# Sheet2.net
KiCad netlist of a schematic drawn in Altium Designer
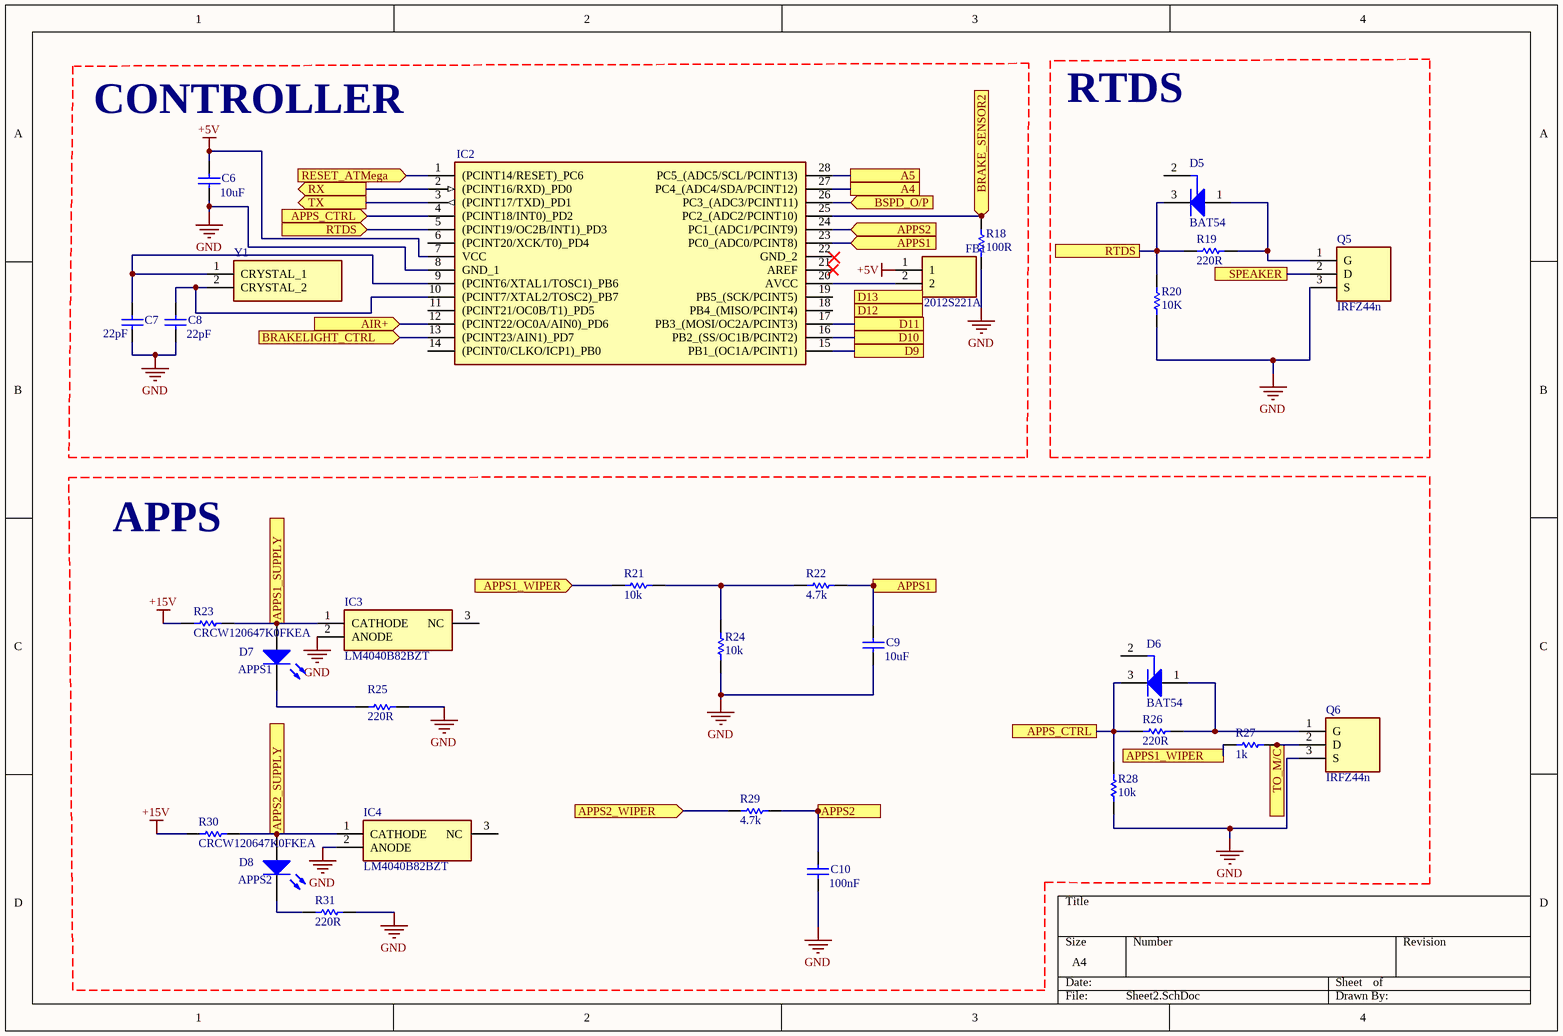
[diagram p0: Sheet2.SchDoc]

(export (version "E")
  (design (tool "Eeschema 10.0.6"))
  (components
    (comp (ref "C6")
      (value "10uF")
      (footprint "KEMT-1206-2_N")
      (description "CAP, Ceramic, 0.1 uF, +/- 10%, 50 V, -55 to 125 degC, 1206 (3216 Metric), RoHS, Tape and Reel")
      (fields (field (name "MANUFACTURER") "Kemet"))
      (libsource (lib "Schlib1_TSAL_LV_3.1") (part "CMP-1037-04202-2"))
    )
    (comp (ref "C7")
      (value "22pF")
      (footprint "KEMT-1206-2_N")
      (description "CAP, Ceramic, 0.1 uF, +/- 10%, 50 V, -55 to 125 degC, 1206 (3216 Metric), RoHS, Tape and Reel")
      (fields (field (name "MANUFACTURER") "Kemet"))
      (libsource (lib "Schlib1_TSAL_LV_3.1") (part "CMP-1037-04202-2"))
    )
    (comp (ref "C8")
      (value "22pF")
      (footprint "KEMT-1206-2_N")
      (description "CAP, Ceramic, 0.1 uF, +/- 10%, 50 V, -55 to 125 degC, 1206 (3216 Metric), RoHS, Tape and Reel")
      (fields (field (name "MANUFACTURER") "Kemet"))
      (libsource (lib "Schlib1_TSAL_LV_3.1") (part "CMP-1037-04202-2"))
    )
    (comp (ref "C9")
      (value "10uF")
      (footprint "KEMT-1206-2_N")
      (description "CAP, Ceramic, 0.1 uF, +/- 10%, 50 V, -55 to 125 degC, 1206 (3216 Metric), RoHS, Tape and Reel")
      (fields (field (name "MANUFACTURER") "Kemet"))
      (libsource (lib "Schlib1_TSAL_LV_3.1") (part "CMP-1037-04202-2"))
    )
    (comp (ref "C10")
      (value "100nF")
      (footprint "KEMT-1206-2_N")
      (description "CAP, Ceramic, 0.1 uF, +/- 10%, 50 V, -55 to 125 degC, 1206 (3216 Metric), RoHS, Tape and Reel")
      (fields (field (name "MANUFACTURER") "Kemet"))
      (libsource (lib "Schlib1_TSAL_LV_3.1") (part "CMP-1037-04202-2"))
    )
    (comp (ref "D5")
      (value "BAT54")
      (footprint "INF-SOT23_N")
      (description "Silicon Schottky Diode, SOT23, Reel, Green")
      (fields (field (name "MANUFACTURER") "Infineon"))
      (libsource (lib "Schlib1_TSAL_LV_3.1") (part "CMP-1182-00010-1"))
    )
    (comp (ref "D6")
      (value "BAT54")
      (footprint "INF-SOT23_N")
      (description "Silicon Schottky Diode, SOT23, Reel, Green")
      (fields (field (name "MANUFACTURER") "Infineon"))
      (libsource (lib "Schlib1_TSAL_LV_3.1") (part "CMP-1182-00010-1"))
    )
    (comp (ref "D7")
      (value "APPS1")
      (footprint "3.2X1.6X1.1")
      (description "Typical RED, GREEN, YELLOW, AMBER GaAs LED")
      (fields (field (name "PUBLISHER") "Altium Limited"))
      (libsource (lib "Miscellaneous Devices") (part "LED2"))
    )
    (comp (ref "D8")
      (value "APPS2")
      (footprint "3.2X1.6X1.1")
      (description "Typical RED, GREEN, YELLOW, AMBER GaAs LED")
      (fields (field (name "PUBLISHER") "Altium Limited"))
      (libsource (lib "Miscellaneous Devices") (part "LED2"))
    )
    (comp (ref "FB1")
      (value "MPZ2012S221A")
      (footprint "SamacSys:BEADC2012X105N")
      (description "Ferrite Bead")
      (fields (field (name "MOUSER PART NUMBER") "810-MPZ2012S221A"))
      (libsource (lib "*") (part "MPZ2012S221A"))
    )
    (comp (ref "IC2")
      (value "ATMEGA328-PU")
      (footprint "SamacSys:DIP1016W53P254L3468H457Q28N")
      (description "Integrated Circuit")
      (fields (field (name "MOUSER PART NUMBER") "556-ATMEGA328-PU"))
      (libsource (lib "*") (part "ATMEGA328-PU"))
    )
    (comp (ref "IC3")
      (value "LM4040B82BZT")
      (footprint "SamacSys:SOT95P237X112-3N")
      (description "Integrated Circuit")
      (fields
        (field (name "MANUFACTURER_PART_NUMBER") "LM4040B25IDBZT")
        (field (name "MOUSER PART NUMBER") "595-LM4040B25IDBZT")
      )
      (libsource (lib "*") (part "LM4040B25IDBZT"))
    )
    (comp (ref "IC4")
      (value "LM4040B82BZT")
      (footprint "SamacSys:SOT95P237X112-3N")
      (description "Integrated Circuit")
      (fields
        (field (name "MANUFACTURER_PART_NUMBER") "LM4040B25IDBZT")
        (field (name "MOUSER PART NUMBER") "595-LM4040B25IDBZT")
      )
      (libsource (lib "*") (part "LM4040B25IDBZT"))
    )
    (comp (ref "Q5")
      (value "IRFZ44n")
      (footprint "SamacSys:TO254P483X1016X2223-3P")
      (description "Transistor")
      (libsource (lib "*") (part "IRFZ44n"))
    )
    (comp (ref "Q6")
      (value "IRFZ44n")
      (footprint "SamacSys:TO254P483X1016X2223-3P")
      (description "Transistor")
      (libsource (lib "*") (part "IRFZ44n"))
    )
    (comp (ref "R18")
      (value "100R")
      (footprint "R1206")
      (fields (field (name "PART NUMBER") "CRCW120647K0FKEA") (field (name "MANUFACTURER") "Vishay Dale"))
      (libsource (lib "Schlib1") (part "RES"))
    )
    (comp (ref "R19")
      (value "220R")
      (footprint "R1206")
      (fields (field (name "PART NUMBER") "CRCW120647K0FKEA") (field (name "MANUFACTURER") "Vishay Dale"))
      (libsource (lib "Schlib1") (part "RES"))
    )
    (comp (ref "R20")
      (value "10K")
      (footprint "R1206")
      (fields (field (name "PART NUMBER") "CRCW120647K0FKEA") (field (name "MANUFACTURER") "Vishay Dale"))
      (libsource (lib "Schlib1") (part "RES"))
    )
    (comp (ref "R21")
      (value "10k")
      (footprint "R1206")
      (fields (field (name "PART NUMBER") "CRCW120647K0FKEA") (field (name "MANUFACTURER") "Vishay Dale"))
      (libsource (lib "Schlib1") (part "RES"))
    )
    (comp (ref "R22")
      (value "4.7k")
      (footprint "R1206")
      (fields (field (name "PART NUMBER") "CRCW120647K0FKEA") (field (name "MANUFACTURER") "Vishay Dale"))
      (libsource (lib "Schlib1") (part "RES"))
    )
    (comp (ref "R23")
      (value "CRCW120647K0FKEA")
      (footprint "R1206")
      (fields (field (name "MANUFACTURER") "Vishay Dale"))
      (libsource (lib "Schlib1") (part "RES"))
    )
    (comp (ref "R24")
      (value "10k")
      (footprint "R1206")
      (fields (field (name "PART NUMBER") "CRCW120647K0FKEA") (field (name "MANUFACTURER") "Vishay Dale"))
      (libsource (lib "Schlib1") (part "RES"))
    )
    (comp (ref "R25")
      (value "220R")
      (footprint "R1206")
      (fields (field (name "PART NUMBER") "CRCW120647K0FKEA") (field (name "MANUFACTURER") "Vishay Dale"))
      (libsource (lib "Schlib1") (part "RES"))
    )
    (comp (ref "R26")
      (value "220R")
      (footprint "R1206")
      (fields (field (name "PART NUMBER") "CRCW120647K0FKEA") (field (name "MANUFACTURER") "Vishay Dale"))
      (libsource (lib "Schlib1") (part "RES"))
    )
    (comp (ref "R27")
      (value "1k")
      (footprint "R1206")
      (fields (field (name "PART NUMBER") "CRCW120647K0FKEA") (field (name "MANUFACTURER") "Vishay Dale"))
      (libsource (lib "Schlib1") (part "RES"))
    )
    (comp (ref "R28")
      (value "10k")
      (footprint "R1206")
      (fields (field (name "PART NUMBER") "CRCW120647K0FKEA") (field (name "MANUFACTURER") "Vishay Dale"))
      (libsource (lib "Schlib1") (part "RES"))
    )
    (comp (ref "R29")
      (value "4.7k")
      (footprint "R1206")
      (fields (field (name "PART NUMBER") "CRCW120647K0FKEA") (field (name "MANUFACTURER") "Vishay Dale"))
      (libsource (lib "Schlib1") (part "RES"))
    )
    (comp (ref "R30")
      (value "CRCW120647K0FKEA")
      (footprint "R1206")
      (fields (field (name "MANUFACTURER") "Vishay Dale"))
      (libsource (lib "Schlib1") (part "RES"))
    )
    (comp (ref "R31")
      (value "220R")
      (footprint "R1206")
      (fields (field (name "PART NUMBER") "CRCW120647K0FKEA") (field (name "MANUFACTURER") "Vishay Dale"))
      (libsource (lib "Schlib1") (part "RES"))
    )
    (comp (ref "Y1")
      (value "ECS-160-18-4X-CKM")
      (footprint "SamacSys:ECS160184XCKM")
      (description "Crystal or Oscillator")
      (fields (field (name "MOUSER PART NUMBER") "520-ECS160-18-4X-CKM"))
      (libsource (lib "*") (part "ECS-160-18-4X-CKM"))
    )
  )
  (nets
    (net (code "1") (name "+5V") (class "Default")
      (node (ref "C6") (pin "2") (pinfunction "2_2") (pintype "passive"))
      (node (ref "FB1") (pin "1") (pinfunction "1_1") (pintype "passive"))
      (node (ref "IC2") (pin "7") (pinfunction "VCC_7") (pintype "power_in"))
    )
    (net (code "2") (name "+15V") (class "Default")
      (node (ref "R23") (pin "1") (pinfunction "1_1") (pintype "passive"))
      (node (ref "R30") (pin "1") (pinfunction "1_1") (pintype "passive"))
    )
    (net (code "3") (name "/A4") (class "Default")
      (node (ref "IC2") (pin "27") (pinfunction "PC4_(ADC4/SDA/PCINT12)_27") (pintype "passive"))
    )
    (net (code "4") (name "/A5") (class "Default")
      (node (ref "IC2") (pin "28") (pinfunction "PC5_(ADC5/SCL/PCINT13)_28") (pintype "passive"))
    )
    (net (code "5") (name "/AIR+") (class "Default")
      (node (ref "IC2") (pin "12") (pinfunction "(PCINT22/OC0A/AIN0)_PD6_12") (pintype "passive"))
    )
    (net (code "6") (name "/APPS1") (class "Default")
      (node (ref "C9") (pin "2") (pinfunction "2_2") (pintype "passive"))
      (node (ref "IC2") (pin "23") (pinfunction "PC0_(ADC0/PCINT8)_23") (pintype "passive"))
      (node (ref "R22") (pin "2") (pinfunction "2_2") (pintype "passive"))
    )
    (net (code "7") (name "/APPS1_SUPPLY") (class "Default")
      (node (ref "D7") (pin "1") (pinfunction "A_1") (pintype "passive"))
      (node (ref "IC3") (pin "1") (pinfunction "CATHODE_1") (pintype "passive"))
      (node (ref "R23") (pin "2") (pinfunction "2_2") (pintype "passive"))
    )
    (net (code "8") (name "/APPS1_WIPER") (class "Default")
      (node (ref "R21") (pin "1") (pinfunction "1_1") (pintype "passive"))
      (node (ref "R27") (pin "2") (pinfunction "2_2") (pintype "passive"))
    )
    (net (code "9") (name "/APPS2") (class "Default")
      (node (ref "C10") (pin "2") (pinfunction "2_2") (pintype "passive"))
      (node (ref "IC2") (pin "24") (pinfunction "PC1_(ADC1/PCINT9)_24") (pintype "passive"))
      (node (ref "R29") (pin "2") (pinfunction "2_2") (pintype "passive"))
    )
    (net (code "10") (name "/APPS2_SUPPLY") (class "Default")
      (node (ref "D8") (pin "1") (pinfunction "A_1") (pintype "passive"))
      (node (ref "IC4") (pin "1") (pinfunction "CATHODE_1") (pintype "passive"))
      (node (ref "R30") (pin "2") (pinfunction "2_2") (pintype "passive"))
    )
    (net (code "11") (name "/APPS2_WIPER") (class "Default")
      (node (ref "R29") (pin "1") (pinfunction "1_1") (pintype "passive"))
    )
    (net (code "12") (name "/APPS_CTRL") (class "Default")
      (node (ref "D6") (pin "3") (pinfunction "K_3") (pintype "passive"))
      (node (ref "IC2") (pin "4") (pinfunction "(PCINT18/INT0)_PD2_4") (pintype "passive"))
      (node (ref "R26") (pin "1") (pinfunction "1_1") (pintype "passive"))
      (node (ref "R28") (pin "2") (pinfunction "2_2") (pintype "passive"))
    )
    (net (code "13") (name "/BRAKELIGHT_CTRL") (class "Default")
      (node (ref "IC2") (pin "13") (pinfunction "(PCINT23/AIN1)_PD7_13") (pintype "passive"))
    )
    (net (code "14") (name "/BRAKE_SENSOR2") (class "Default")
      (node (ref "IC2") (pin "25") (pinfunction "PC2_(ADC2/PCINT10)_25") (pintype "passive"))
      (node (ref "R18") (pin "2") (pinfunction "2_2") (pintype "passive"))
    )
    (net (code "15") (name "/BSPD_O{slash}P") (class "Default")
      (node (ref "IC2") (pin "26") (pinfunction "PC3_(ADC3/PCINT11)_26") (pintype "passive"))
    )
    (net (code "16") (name "/D9") (class "Default")
      (node (ref "IC2") (pin "15") (pinfunction "PB1_(OC1A/PCINT1)_15") (pintype "passive"))
    )
    (net (code "17") (name "/D10") (class "Default")
      (node (ref "IC2") (pin "16") (pinfunction "PB2_(SS/OC1B/PCINT2)_16") (pintype "passive"))
    )
    (net (code "18") (name "/D11") (class "Default")
      (node (ref "IC2") (pin "17") (pinfunction "PB3_(MOSI/OC2A/PCINT3)_17") (pintype "passive"))
    )
    (net (code "21") (name "/RESET_ATMega") (class "Default")
      (node (ref "IC2") (pin "1") (pinfunction "(PCINT14/RESET)_PC6_1") (pintype "passive"))
    )
    (net (code "22") (name "/RTDS") (class "Default")
      (node (ref "D5") (pin "3") (pinfunction "K_3") (pintype "passive"))
      (node (ref "IC2") (pin "5") (pinfunction "(PCINT19/OC2B/INT1)_PD3_5") (pintype "passive"))
      (node (ref "R19") (pin "1") (pinfunction "1_1") (pintype "passive"))
      (node (ref "R20") (pin "2") (pinfunction "2_2") (pintype "passive"))
    )
    (net (code "23") (name "/RX") (class "Default")
      (node (ref "IC2") (pin "2") (pinfunction "(PCINT16/RXD)_PD0_2") (pintype "input"))
    )
    (net (code "24") (name "/SPEAKER") (class "Default")
      (node (ref "Q5") (pin "2") (pinfunction "D_2") (pintype "passive"))
    )
    (net (code "25") (name "/TO_M{slash}C") (class "Default")
      (node (ref "Q6") (pin "2") (pinfunction "D_2") (pintype "passive"))
      (node (ref "R27") (pin "1") (pinfunction "1_1") (pintype "passive"))
    )
    (net (code "26") (name "/TX") (class "Default")
      (node (ref "IC2") (pin "3") (pinfunction "(PCINT17/TXD)_PD1_3") (pintype "output"))
    )
    (net (code "27") (name "GND") (class "Default")
      (node (ref "C10") (pin "1") (pinfunction "1_1") (pintype "passive"))
      (node (ref "C6") (pin "1") (pinfunction "1_1") (pintype "passive"))
      (node (ref "C7") (pin "1") (pinfunction "1_1") (pintype "passive"))
      (node (ref "C8") (pin "1") (pinfunction "1_1") (pintype "passive"))
      (node (ref "C9") (pin "1") (pinfunction "1_1") (pintype "passive"))
      (node (ref "IC2") (pin "8") (pinfunction "GND_1_8") (pintype "power_in"))
      (node (ref "IC3") (pin "2") (pinfunction "ANODE_2") (pintype "passive"))
      (node (ref "IC4") (pin "2") (pinfunction "ANODE_2") (pintype "passive"))
      (node (ref "Q5") (pin "3") (pinfunction "S_3") (pintype "passive"))
      (node (ref "Q6") (pin "3") (pinfunction "S_3") (pintype "passive"))
      (node (ref "R18") (pin "1") (pinfunction "1_1") (pintype "passive"))
      (node (ref "R20") (pin "1") (pinfunction "1_1") (pintype "passive"))
      (node (ref "R24") (pin "1") (pinfunction "1_1") (pintype "passive"))
      (node (ref "R25") (pin "2") (pinfunction "2_2") (pintype "passive"))
      (node (ref "R28") (pin "1") (pinfunction "1_1") (pintype "passive"))
      (node (ref "R31") (pin "2") (pinfunction "2_2") (pintype "passive"))
    )
    (net (code "28") (name "Net-(D5-A)") (class "Default")
      (node (ref "D5") (pin "1") (pinfunction "A_1") (pintype "passive"))
      (node (ref "Q5") (pin "1") (pinfunction "G_1") (pintype "passive"))
      (node (ref "R19") (pin "2") (pinfunction "2_2") (pintype "passive"))
    )
    (net (code "29") (name "Net-(D6-A)") (class "Default")
      (node (ref "D6") (pin "1") (pinfunction "A_1") (pintype "passive"))
      (node (ref "Q6") (pin "1") (pinfunction "G_1") (pintype "passive"))
      (node (ref "R26") (pin "2") (pinfunction "2_2") (pintype "passive"))
    )
    (net (code "30") (name "Net-(D7-K)") (class "Default")
      (node (ref "D7") (pin "2") (pinfunction "K_2") (pintype "passive"))
      (node (ref "R25") (pin "1") (pinfunction "1_1") (pintype "passive"))
    )
    (net (code "31") (name "Net-(D8-K)") (class "Default")
      (node (ref "D8") (pin "2") (pinfunction "K_2") (pintype "passive"))
      (node (ref "R31") (pin "1") (pinfunction "1_1") (pintype "passive"))
    )
    (net (code "32") (name "Net-(IC2-(PCINT6{slash}XTAL1{slash}TOSC1)_PB6)") (class "Default")
      (node (ref "C7") (pin "2") (pinfunction "2_2") (pintype "passive"))
      (node (ref "IC2") (pin "9") (pinfunction "(PCINT6/XTAL1/TOSC1)_PB6_9") (pintype "passive"))
      (node (ref "Y1") (pin "1") (pinfunction "CRYSTAL_1_1") (pintype "passive"))
    )
    (net (code "33") (name "Net-(IC2-(PCINT7{slash}XTAL2{slash}TOSC2)_PB7)") (class "Default")
      (node (ref "C8") (pin "2") (pinfunction "2_2") (pintype "passive"))
      (node (ref "IC2") (pin "10") (pinfunction "(PCINT7/XTAL2/TOSC2)_PB7_10") (pintype "passive"))
      (node (ref "Y1") (pin "2") (pinfunction "CRYSTAL_2_2") (pintype "passive"))
    )
    (net (code "34") (name "Net-(IC2-AVCC)") (class "Default")
      (node (ref "FB1") (pin "2") (pinfunction "2_2") (pintype "passive"))
      (node (ref "IC2") (pin "20") (pinfunction "AVCC_20") (pintype "power_in"))
    )
    (net (code "35") (name "Net-(R21-Pad2)") (class "Default")
      (node (ref "R21") (pin "2") (pinfunction "2_2") (pintype "passive"))
      (node (ref "R22") (pin "1") (pinfunction "1_1") (pintype "passive"))
      (node (ref "R24") (pin "2") (pinfunction "2_2") (pintype "passive"))
    )
    (net (code "36") (name "unconnected-(D5-NC-Pad2)") (class "Default")
      (node (ref "D5") (pin "2") (pinfunction "NC_2") (pintype "passive"))
    )
    (net (code "37") (name "unconnected-(D6-NC-Pad2)") (class "Default")
      (node (ref "D6") (pin "2") (pinfunction "NC_2") (pintype "passive"))
    )
    (net (code "38") (name "unconnected-(IC2-(PCINT0{slash}CLKO{slash}ICP1)_PB0-Pad14)") (class "Default")
      (node (ref "IC2") (pin "14") (pinfunction "(PCINT0/CLKO/ICP1)_PB0_14") (pintype "passive"))
    )
    (net (code "39") (name "unconnected-(IC2-(PCINT20{slash}XCK{slash}T0)_PD4-Pad6)") (class "Default")
      (node (ref "IC2") (pin "6") (pinfunction "(PCINT20/XCK/T0)_PD4_6") (pintype "passive"))
    )
    (net (code "40") (name "unconnected-(IC2-(PCINT21{slash}OC0B{slash}T1)_PD5-Pad11)") (class "Default")
      (node (ref "IC2") (pin "11") (pinfunction "(PCINT21/OC0B/T1)_PD5_11") (pintype "passive"))
    )
    (net (code "41") (name "unconnected-(IC2-AREF-Pad21)") (class "Default")
      (node (ref "IC2") (pin "21") (pinfunction "AREF_21") (pintype "passive+no_connect"))
    )
    (net (code "42") (name "unconnected-(IC2-GND_2-Pad22)") (class "Default")
      (node (ref "IC2") (pin "22") (pinfunction "GND_2_22") (pintype "power_in"))
    )
    (net (code "43") (name "unconnected-(IC2-PB4_(MISO{slash}PCINT4)-Pad18)") (class "Default")
      (node (ref "IC2") (pin "18") (pinfunction "PB4_(MISO/PCINT4)_18") (pintype "passive"))
    )
    (net (code "44") (name "unconnected-(IC2-PB5_(SCK{slash}PCINT5)-Pad19)") (class "Default")
      (node (ref "IC2") (pin "19") (pinfunction "PB5_(SCK/PCINT5)_19") (pintype "passive"))
    )
    (net (code "45") (name "unconnected-(IC3-NC-Pad3)") (class "Default")
      (node (ref "IC3") (pin "3") (pinfunction "NC_3") (pintype "passive"))
    )
    (net (code "46") (name "unconnected-(IC4-NC-Pad3)") (class "Default")
      (node (ref "IC4") (pin "3") (pinfunction "NC_3") (pintype "passive"))
    )
  )
)
